# BS.net
KiCad netlist of a schematic drawn in Altium Designer
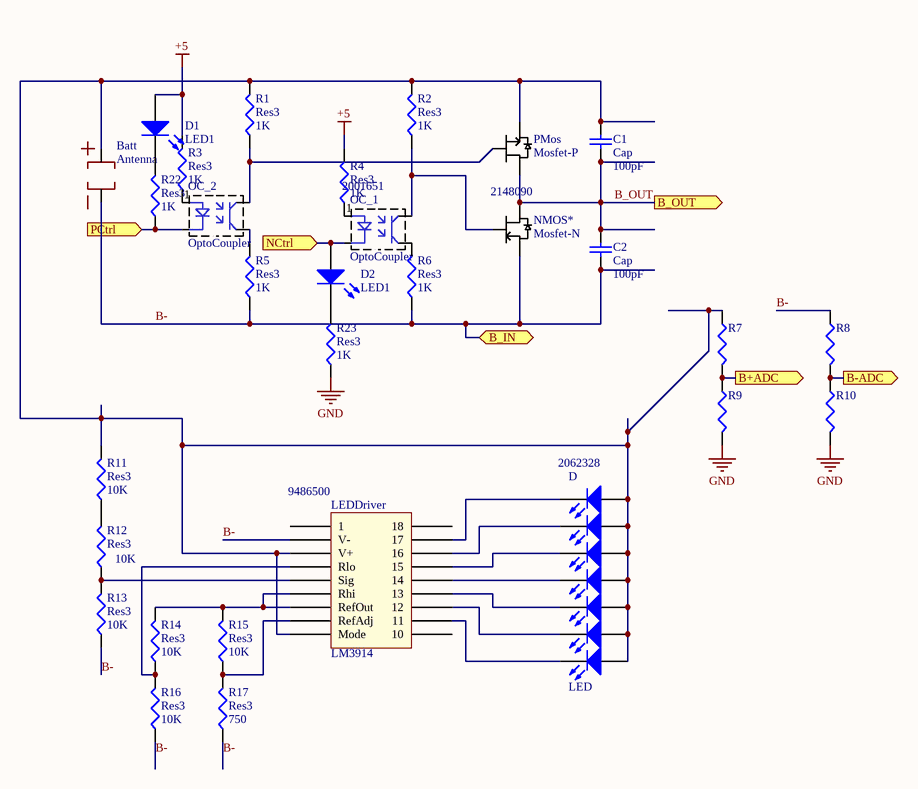
[diagram p0: BS.SchDoc]

(export (version "E")
  (design (tool "Eeschema 10.0.6"))
  (components
    (comp (ref "Batt")
      (value "Antenna")
      (footprint "18650_PCB_HOLDER")
      (libsource (lib "Custom") (part "BATTERYHOLDER"))
    )
    (comp (ref "C1")
      (value "Cap")
      (footprint "6-0805_L")
      (description "Capacitor")
      (fields (field (name "ALTIUM_VALUE") "100pF") (field (name "PUBLISHER") "Altium Limited"))
      (libsource (lib "Miscellaneous Devices") (part "Cap"))
    )
    (comp (ref "C2")
      (value "Cap")
      (footprint "6-0805_L")
      (description "Capacitor")
      (fields (field (name "ALTIUM_VALUE") "100pF") (field (name "PUBLISHER") "Altium Limited"))
      (libsource (lib "Miscellaneous Devices") (part "Cap"))
    )
    (comp (ref "D")
      (value "LED")
      (footprint "LED Strip")
      (fields (field (name "SUPPLIER PART NUMBER 1") "2062328"))
      (libsource (lib "Custom") (part "LEDStrip"))
    )
    (comp (ref "D1")
      (value "LED1")
      (footprint "LED")
      (description "Typical RED GaAs LED")
      (fields (field (name "PUBLISHER") "Altium Limited"))
      (libsource (lib "Miscellaneous Devices") (part "LED1"))
    )
    (comp (ref "D2")
      (value "LED1")
      (footprint "LED")
      (description "Typical RED GaAs LED")
      (fields (field (name "PUBLISHER") "Altium Limited"))
      (libsource (lib "Miscellaneous Devices") (part "LED1"))
    )
    (comp (ref "LEDDriver")
      (value "LM3914")
      (footprint "DIP18")
      (fields (field (name "SUPPLIER PART NUMBER 1") "9486500"))
      (libsource (lib "Custom") (part "LM3914"))
    )
    (comp (ref "NMOS*")
      (value "Mosfet-N")
      (footprint "MOSFET")
      (fields (field (name "SUPPLIER PART NUMBER 1") "2148090"))
      (libsource (lib "Custom") (part "Mosfet-N"))
    )
    (comp (ref "OC_1")
      (value "OptoCoupler")
      (footprint "SMDIP4")
      (fields (field (name "SUPPLIER PART NUMBER 1") "2001651"))
      (libsource (lib "Custom") (part "OptoCoupler"))
    )
    (comp (ref "OC_2")
      (value "OptoCoupler")
      (footprint "SMDIP4")
      (libsource (lib "Custom") (part "OptoCoupler"))
    )
    (comp (ref "PMos") (value "Mosfet-P") (footprint "MOSFET") (libsource (lib "Custom") (part "Mosfet-P")))
    (comp (ref "R1")
      (value "Res3")
      (footprint "J1-0603")
      (description "Resistor")
      (fields (field (name "ALTIUM_VALUE") "1K") (field (name "PUBLISHER") "Altium Limited"))
      (libsource (lib "Miscellaneous Devices") (part "Res3"))
    )
    (comp (ref "R2")
      (value "Res3")
      (footprint "J1-0603")
      (description "Resistor")
      (fields (field (name "ALTIUM_VALUE") "1K") (field (name "PUBLISHER") "Altium Limited"))
      (libsource (lib "Miscellaneous Devices") (part "Res3"))
    )
    (comp (ref "R3")
      (value "Res3")
      (footprint "J1-0603")
      (description "Resistor")
      (fields (field (name "ALTIUM_VALUE") "1K") (field (name "PUBLISHER") "Altium Limited"))
      (libsource (lib "Miscellaneous Devices") (part "Res3"))
    )
    (comp (ref "R4")
      (value "Res3")
      (footprint "J1-0603")
      (description "Resistor")
      (fields (field (name "ALTIUM_VALUE") "1K") (field (name "PUBLISHER") "Altium Limited"))
      (libsource (lib "Miscellaneous Devices") (part "Res3"))
    )
    (comp (ref "R5")
      (value "Res3")
      (footprint "J1-0603")
      (description "Resistor")
      (fields (field (name "ALTIUM_VALUE") "1K") (field (name "PUBLISHER") "Altium Limited"))
      (libsource (lib "Miscellaneous Devices") (part "Res3"))
    )
    (comp (ref "R6")
      (value "Res3")
      (footprint "J1-0603")
      (description "Resistor")
      (fields (field (name "ALTIUM_VALUE") "1K") (field (name "PUBLISHER") "Altium Limited"))
      (libsource (lib "Miscellaneous Devices") (part "Res3"))
    )
    (comp (ref "R7")
      (value "Res3")
      (footprint "J1-0603")
      (description "Resistor")
      (fields (field (name "PUBLISHER") "Altium Limited"))
      (libsource (lib "Miscellaneous Devices") (part "Res3"))
    )
    (comp (ref "R8")
      (value "Res3")
      (footprint "J1-0603")
      (description "Resistor")
      (fields (field (name "PUBLISHER") "Altium Limited"))
      (libsource (lib "Miscellaneous Devices") (part "Res3"))
    )
    (comp (ref "R9")
      (value "Res3")
      (footprint "J1-0603")
      (description "Resistor")
      (fields (field (name "PUBLISHER") "Altium Limited"))
      (libsource (lib "Miscellaneous Devices") (part "Res3"))
    )
    (comp (ref "R10")
      (value "Res3")
      (footprint "J1-0603")
      (description "Resistor")
      (fields (field (name "PUBLISHER") "Altium Limited"))
      (libsource (lib "Miscellaneous Devices") (part "Res3"))
    )
    (comp (ref "R11")
      (value "Res3")
      (footprint "J1-0603")
      (description "Resistor")
      (fields (field (name "ALTIUM_VALUE") "10K") (field (name "PUBLISHER") "Altium Limited"))
      (libsource (lib "Miscellaneous Devices") (part "Res3"))
    )
    (comp (ref "R12")
      (value "Res3")
      (footprint "J1-0603")
      (description "Resistor")
      (fields (field (name "ALTIUM_VALUE") "10K") (field (name "PUBLISHER") "Altium Limited"))
      (libsource (lib "Miscellaneous Devices") (part "Res3"))
    )
    (comp (ref "R13")
      (value "Res3")
      (footprint "J1-0603")
      (description "Resistor")
      (fields (field (name "ALTIUM_VALUE") "10K") (field (name "PUBLISHER") "Altium Limited"))
      (libsource (lib "Miscellaneous Devices") (part "Res3"))
    )
    (comp (ref "R14")
      (value "Res3")
      (footprint "J1-0603")
      (description "Resistor")
      (fields (field (name "ALTIUM_VALUE") "10K") (field (name "PUBLISHER") "Altium Limited"))
      (libsource (lib "Miscellaneous Devices") (part "Res3"))
    )
    (comp (ref "R15")
      (value "Res3")
      (footprint "J1-0603")
      (description "Resistor")
      (fields (field (name "ALTIUM_VALUE") "10K") (field (name "PUBLISHER") "Altium Limited"))
      (libsource (lib "Miscellaneous Devices") (part "Res3"))
    )
    (comp (ref "R16")
      (value "Res3")
      (footprint "J1-0603")
      (description "Resistor")
      (fields (field (name "ALTIUM_VALUE") "10K") (field (name "PUBLISHER") "Altium Limited"))
      (libsource (lib "Miscellaneous Devices") (part "Res3"))
    )
    (comp (ref "R17")
      (value "Res3")
      (footprint "J1-0603")
      (description "Resistor")
      (fields (field (name "ALTIUM_VALUE") "750") (field (name "PUBLISHER") "Altium Limited"))
      (libsource (lib "Miscellaneous Devices") (part "Res3"))
    )
    (comp (ref "R22")
      (value "Res3")
      (footprint "J1-0603")
      (description "Resistor")
      (fields (field (name "ALTIUM_VALUE") "1K") (field (name "PUBLISHER") "Altium Limited"))
      (libsource (lib "Miscellaneous Devices") (part "Res3"))
    )
    (comp (ref "R23")
      (value "Res3")
      (footprint "J1-0603")
      (description "Resistor")
      (fields (field (name "ALTIUM_VALUE") "1K") (field (name "PUBLISHER") "Altium Limited"))
      (libsource (lib "Miscellaneous Devices") (part "Res3"))
    )
  )
  (nets
    (net (code "1") (name "+5") (class "Default")
      (node (ref "D1") (pin "1") (pinfunction "A_1") (pintype "passive"))
      (node (ref "R3") (pin "2") (pinfunction "2_2") (pintype "passive"))
      (node (ref "R4") (pin "2") (pinfunction "2_2") (pintype "passive"))
    )
    (net (code "2") (name "/B+ADC") (class "Default")
      (node (ref "R7") (pin "2") (pinfunction "2_2") (pintype "passive"))
      (node (ref "R9") (pin "2") (pinfunction "2_2") (pintype "passive"))
    )
    (net (code "3") (name "/B-") (class "Default")
      (node (ref "Batt") (pin "N") (pinfunction "N_N") (pintype "passive"))
      (node (ref "C2") (pin "1") (pinfunction "1_1") (pintype "passive"))
      (node (ref "LEDDriver") (pin "2") (pinfunction "V-_2") (pintype "passive"))
      (node (ref "NMOS*") (pin "3") (pinfunction "Source_3") (pintype "passive"))
      (node (ref "R13") (pin "1") (pinfunction "1_1") (pintype "passive"))
      (node (ref "R16") (pin "1") (pinfunction "1_1") (pintype "passive"))
      (node (ref "R17") (pin "1") (pinfunction "1_1") (pintype "passive"))
      (node (ref "R5") (pin "1") (pinfunction "1_1") (pintype "passive"))
      (node (ref "R6") (pin "1") (pinfunction "1_1") (pintype "passive"))
      (node (ref "R8") (pin "1") (pinfunction "1_1") (pintype "passive"))
    )
    (net (code "4") (name "/B-ADC") (class "Default")
      (node (ref "R10") (pin "2") (pinfunction "2_2") (pintype "passive"))
      (node (ref "R8") (pin "2") (pinfunction "2_2") (pintype "passive"))
    )
    (net (code "5") (name "/B_OUT") (class "Default")
      (node (ref "C1") (pin "1") (pinfunction "1_1") (pintype "passive"))
      (node (ref "C2") (pin "2") (pinfunction "2_2") (pintype "passive"))
      (node (ref "NMOS*") (pin "2") (pinfunction "Drain_2") (pintype "passive"))
      (node (ref "PMos") (pin "3") (pinfunction "3_3") (pintype "passive"))
    )
    (net (code "6") (name "/NCtrl") (class "Default")
      (node (ref "D2") (pin "1") (pinfunction "A_1") (pintype "passive"))
      (node (ref "OC_1") (pin "2") (pinfunction "2_2") (pintype "passive"))
    )
    (net (code "7") (name "/PCtrl") (class "Default")
      (node (ref "OC_2") (pin "2") (pinfunction "2_2") (pintype "passive"))
      (node (ref "R22") (pin "1") (pinfunction "1_1") (pintype "passive"))
    )
    (net (code "8") (name "GND") (class "Default")
      (node (ref "R10") (pin "1") (pinfunction "1_1") (pintype "passive"))
      (node (ref "R23") (pin "1") (pinfunction "1_1") (pintype "passive"))
      (node (ref "R9") (pin "1") (pinfunction "1_1") (pintype "passive"))
    )
    (net (code "9") (name "Net-(D-K-Pad2)") (class "Default")
      (node (ref "D") (pin "2") (pinfunction "K_2") (pintype "passive"))
      (node (ref "LEDDriver") (pin "11") (pinfunction "11_11") (pintype "passive"))
    )
    (net (code "10") (name "Net-(D-K-Pad4)") (class "Default")
      (node (ref "D") (pin "4") (pinfunction "K_4") (pintype "passive"))
      (node (ref "LEDDriver") (pin "12") (pinfunction "12_12") (pintype "passive"))
    )
    (net (code "11") (name "Net-(D-K-Pad6)") (class "Default")
      (node (ref "D") (pin "6") (pinfunction "K_6") (pintype "passive"))
      (node (ref "LEDDriver") (pin "13") (pinfunction "13_13") (pintype "passive"))
    )
    (net (code "12") (name "Net-(D-K-Pad8)") (class "Default")
      (node (ref "D") (pin "8") (pinfunction "K_8") (pintype "passive"))
      (node (ref "LEDDriver") (pin "14") (pinfunction "14_14") (pintype "passive"))
    )
    (net (code "13") (name "Net-(D-K-Pad10)") (class "Default")
      (node (ref "D") (pin "10") (pinfunction "K_10") (pintype "passive"))
      (node (ref "LEDDriver") (pin "15") (pinfunction "15_15") (pintype "passive"))
    )
    (net (code "14") (name "Net-(D-K-Pad12)") (class "Default")
      (node (ref "D") (pin "12") (pinfunction "K_12") (pintype "passive"))
      (node (ref "LEDDriver") (pin "16") (pinfunction "16_16") (pintype "passive"))
    )
    (net (code "15") (name "Net-(D-K-Pad14)") (class "Default")
      (node (ref "D") (pin "14") (pinfunction "K_14") (pintype "passive"))
      (node (ref "LEDDriver") (pin "17") (pinfunction "17_17") (pintype "passive"))
    )
    (net (code "16") (name "Net-(D1-K)") (class "Default")
      (node (ref "D1") (pin "2") (pinfunction "K_2") (pintype "passive"))
      (node (ref "R22") (pin "2") (pinfunction "2_2") (pintype "passive"))
    )
    (net (code "17") (name "Net-(D2-K)") (class "Default")
      (node (ref "D2") (pin "2") (pinfunction "K_2") (pintype "passive"))
      (node (ref "R23") (pin "2") (pinfunction "2_2") (pintype "passive"))
    )
    (net (code "18") (name "Net-(LEDDriver-Mode)") (class "Default")
      (node (ref "Batt") (pin "P") (pinfunction "P_P") (pintype "passive"))
      (node (ref "C1") (pin "2") (pinfunction "2_2") (pintype "passive"))
      (node (ref "D") (pin "1") (pinfunction "A_1") (pintype "passive"))
      (node (ref "D") (pin "11") (pinfunction "A_11") (pintype "passive"))
      (node (ref "D") (pin "13") (pinfunction "A_13") (pintype "passive"))
      (node (ref "D") (pin "3") (pinfunction "A_3") (pintype "passive"))
      (node (ref "D") (pin "5") (pinfunction "A_5") (pintype "passive"))
      (node (ref "D") (pin "7") (pinfunction "A_7") (pintype "passive"))
      (node (ref "D") (pin "9") (pinfunction "A_9") (pintype "passive"))
      (node (ref "LEDDriver") (pin "3") (pinfunction "V+_3") (pintype "passive"))
      (node (ref "LEDDriver") (pin "9") (pinfunction "Mode_9") (pintype "passive"))
      (node (ref "PMos") (pin "2") (pinfunction "2_2") (pintype "passive"))
      (node (ref "R1") (pin "2") (pinfunction "2_2") (pintype "passive"))
      (node (ref "R11") (pin "2") (pinfunction "2_2") (pintype "passive"))
      (node (ref "R2") (pin "2") (pinfunction "2_2") (pintype "passive"))
      (node (ref "R7") (pin "1") (pinfunction "1_1") (pintype "passive"))
    )
    (net (code "19") (name "Net-(LEDDriver-RefAdj)") (class "Default")
      (node (ref "LEDDriver") (pin "8") (pinfunction "RefAdj_8") (pintype "passive"))
      (node (ref "R15") (pin "1") (pinfunction "1_1") (pintype "passive"))
      (node (ref "R17") (pin "2") (pinfunction "2_2") (pintype "passive"))
    )
    (net (code "20") (name "Net-(LEDDriver-RefOut)") (class "Default")
      (node (ref "LEDDriver") (pin "6") (pinfunction "Rhi_6") (pintype "passive"))
      (node (ref "LEDDriver") (pin "7") (pinfunction "RefOut_7") (pintype "passive"))
      (node (ref "R14") (pin "2") (pinfunction "2_2") (pintype "passive"))
      (node (ref "R15") (pin "2") (pinfunction "2_2") (pintype "passive"))
    )
    (net (code "21") (name "Net-(LEDDriver-Rlo)") (class "Default")
      (node (ref "LEDDriver") (pin "4") (pinfunction "Rlo_4") (pintype "passive"))
      (node (ref "R14") (pin "1") (pinfunction "1_1") (pintype "passive"))
      (node (ref "R16") (pin "2") (pinfunction "2_2") (pintype "passive"))
    )
    (net (code "22") (name "Net-(LEDDriver-Sig)") (class "Default")
      (node (ref "LEDDriver") (pin "5") (pinfunction "Sig_5") (pintype "passive"))
      (node (ref "R12") (pin "1") (pinfunction "1_1") (pintype "passive"))
      (node (ref "R13") (pin "2") (pinfunction "2_2") (pintype "passive"))
    )
    (net (code "23") (name "Net-(NMOS*-Gate)") (class "Default")
      (node (ref "NMOS*") (pin "1") (pinfunction "Gate_1") (pintype "passive"))
      (node (ref "OC_1") (pin "4") (pinfunction "4_4") (pintype "passive"))
      (node (ref "R2") (pin "1") (pinfunction "1_1") (pintype "passive"))
    )
    (net (code "24") (name "Net-(OC_1-Pad1)") (class "Default")
      (node (ref "OC_1") (pin "1") (pinfunction "1_1") (pintype "passive"))
      (node (ref "R4") (pin "1") (pinfunction "1_1") (pintype "passive"))
    )
    (net (code "25") (name "Net-(OC_1-Pad3)") (class "Default")
      (node (ref "OC_1") (pin "3") (pinfunction "3_3") (pintype "passive"))
      (node (ref "R6") (pin "2") (pinfunction "2_2") (pintype "passive"))
    )
    (net (code "26") (name "Net-(OC_2-Pad1)") (class "Default")
      (node (ref "OC_2") (pin "1") (pinfunction "1_1") (pintype "passive"))
      (node (ref "R3") (pin "1") (pinfunction "1_1") (pintype "passive"))
    )
    (net (code "27") (name "Net-(OC_2-Pad3)") (class "Default")
      (node (ref "OC_2") (pin "3") (pinfunction "3_3") (pintype "passive"))
      (node (ref "R5") (pin "2") (pinfunction "2_2") (pintype "passive"))
    )
    (net (code "28") (name "Net-(OC_2-Pad4)") (class "Default")
      (node (ref "OC_2") (pin "4") (pinfunction "4_4") (pintype "passive"))
      (node (ref "PMos") (pin "1") (pinfunction "1_1") (pintype "passive"))
      (node (ref "R1") (pin "1") (pinfunction "1_1") (pintype "passive"))
    )
    (net (code "29") (name "Net-(R11-Pad1)") (class "Default")
      (node (ref "R11") (pin "1") (pinfunction "1_1") (pintype "passive"))
      (node (ref "R12") (pin "2") (pinfunction "2_2") (pintype "passive"))
    )
    (net (code "30") (name "unconnected-(LEDDriver-Pad1)") (class "Default")
      (node (ref "LEDDriver") (pin "1") (pinfunction "1_1") (pintype "passive"))
    )
    (net (code "31") (name "unconnected-(LEDDriver-Pad10)") (class "Default")
      (node (ref "LEDDriver") (pin "10") (pinfunction "10_10") (pintype "passive"))
    )
    (net (code "32") (name "unconnected-(LEDDriver-Pad18)") (class "Default")
      (node (ref "LEDDriver") (pin "18") (pinfunction "18_18") (pintype "passive"))
    )
  )
)
